# Atmega16-platform.net
KiCad netlist of a schematic drawn in Altium Designer
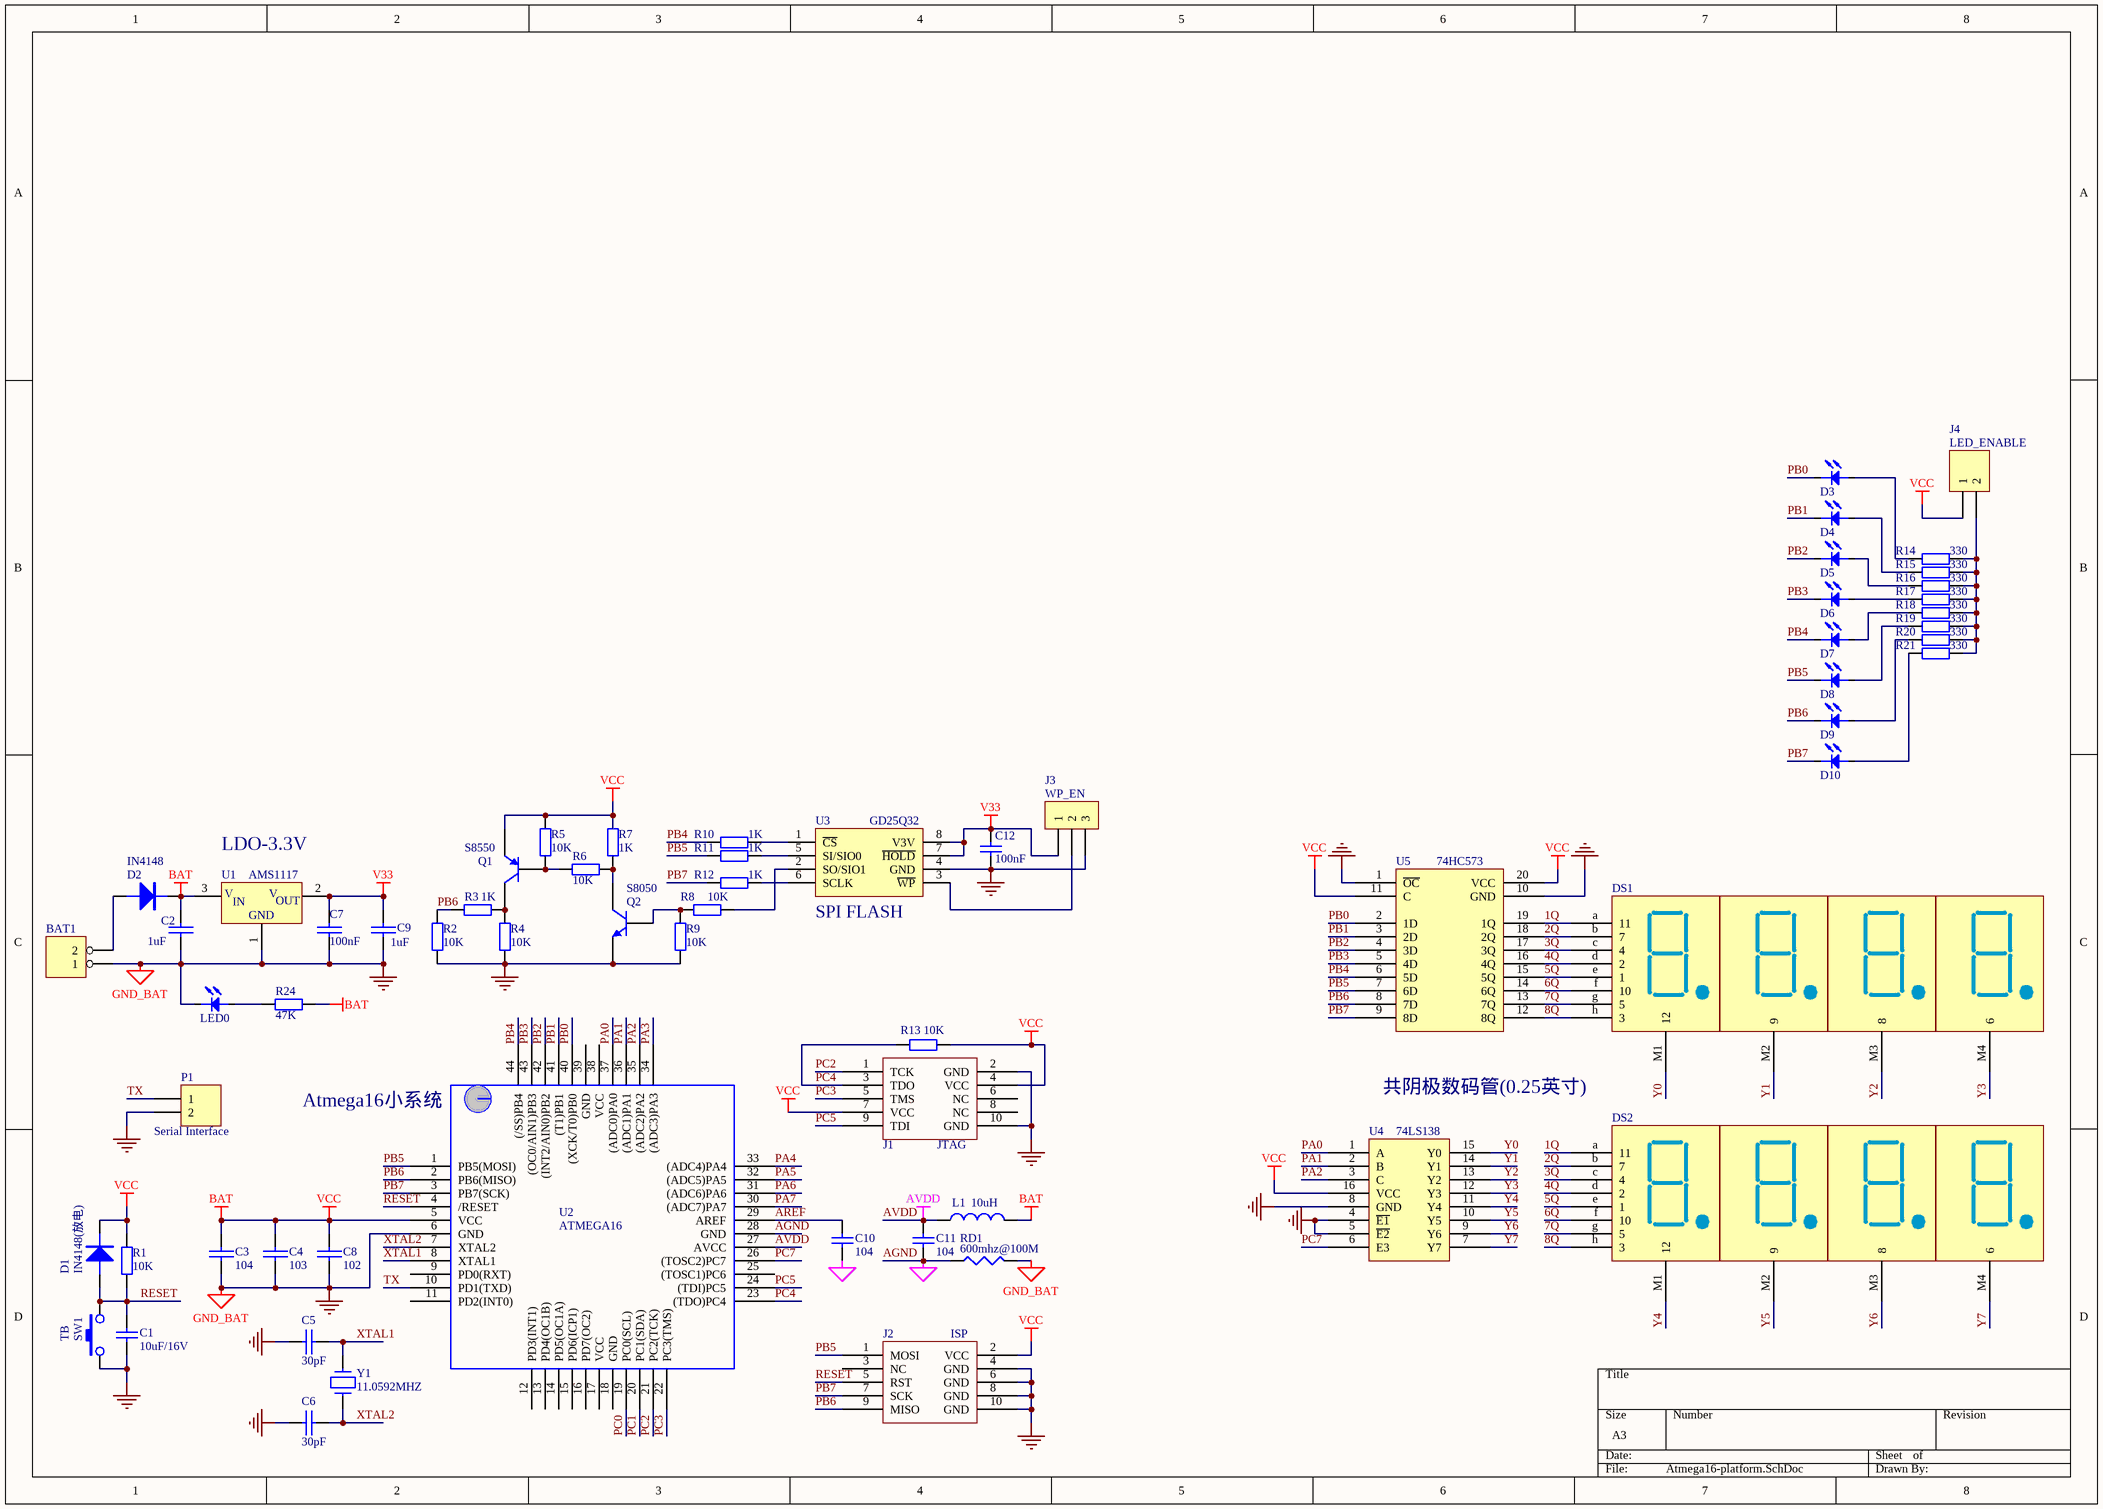
[diagram p0: Atmega16-platform.SchDoc]

(export (version "E")
  (design (tool "Eeschema 10.0.6"))
  (components
    (comp (ref "BAT1") (value "~") (footprint "SIP2") (libsource (lib "*") (part "HEADER 2")))
    (comp (ref "C1")
      (value "10uF/16V")
      (footprint "10uF/50V")
      (description "Capacitor")
      (fields (field (name "PUBLISHER") "Altium Limited"))
      (libsource (lib "*") (part "Cap"))
    )
    (comp (ref "C2")
      (value "1uF")
      (footprint "0805")
      (description "Capacitor")
      (libsource (lib "*") (part "CAP"))
    )
    (comp (ref "C3")
      (value "104")
      (footprint "0603")
      (description "Capacitor")
      (libsource (lib "*") (part "CAP"))
    )
    (comp (ref "C4")
      (value "103")
      (footprint "0603")
      (description "Capacitor")
      (libsource (lib "*") (part "CAP"))
    )
    (comp (ref "C5")
      (value "30pF")
      (footprint "0603")
      (description "Capacitor")
      (libsource (lib "*") (part "CAP"))
    )
    (comp (ref "C6")
      (value "30pF")
      (footprint "0603")
      (description "Capacitor")
      (libsource (lib "*") (part "CAP"))
    )
    (comp (ref "C7")
      (value "100nF")
      (footprint "0603")
      (description "Capacitor")
      (libsource (lib "*") (part "CAP"))
    )
    (comp (ref "C8")
      (value "102")
      (footprint "0603")
      (description "Capacitor")
      (libsource (lib "*") (part "CAP"))
    )
    (comp (ref "C9")
      (value "1uF")
      (footprint "0805")
      (description "Capacitor")
      (libsource (lib "*") (part "CAP"))
    )
    (comp (ref "C10")
      (value "104")
      (footprint "0603")
      (description "Capacitor (Semiconductor SIM Model)")
      (fields (field (name "PUBLISHER") "Altium Limited"))
      (libsource (lib "*") (part "Cap Semi"))
    )
    (comp (ref "C11")
      (value "104")
      (footprint "0603")
      (description "Capacitor (Semiconductor SIM Model)")
      (fields (field (name "PUBLISHER") "Altium Limited"))
      (libsource (lib "*") (part "Cap Semi"))
    )
    (comp (ref "C12")
      (value "100nF")
      (footprint "0603")
      (description "Capacitor")
      (fields (field (name "PUBLISHER") "Altium Limited"))
      (libsource (lib "*") (part "Cap"))
    )
    (comp (ref "D1")
      (value "IN4148(放电)")
      (footprint "SOD-123")
      (description "Diode")
      (libsource (lib "*") (part "DIODE"))
    )
    (comp (ref "D2")
      (value "IN4148")
      (footprint "SOD-123")
      (description "Diode")
      (libsource (lib "*") (part "DIODE"))
    )
    (comp (ref "D3") (value "LED") (footprint "0603") (libsource (lib "常用元件库") (part "LED")))
    (comp (ref "D4") (value "LED") (footprint "0603") (libsource (lib "常用元件库") (part "LED")))
    (comp (ref "D5") (value "LED") (footprint "0603") (libsource (lib "常用元件库") (part "LED")))
    (comp (ref "D6") (value "LED") (footprint "0603") (libsource (lib "常用元件库") (part "LED")))
    (comp (ref "D7") (value "LED") (footprint "0603") (libsource (lib "常用元件库") (part "LED")))
    (comp (ref "D8") (value "LED") (footprint "0603") (libsource (lib "常用元件库") (part "LED")))
    (comp (ref "D9") (value "LED") (footprint "0603") (libsource (lib "常用元件库") (part "LED")))
    (comp (ref "D10") (value "LED") (footprint "0603") (libsource (lib "常用元件库") (part "LED")))
    (comp (ref "DS1")
      (value "LED_8*4_SEG")
      (footprint "4BIT_8SEG_LED")
      (libsource (lib "单片机及相关") (part "LED_8*4_SEG"))
    )
    (comp (ref "DS2")
      (value "LED_8*4_SEG")
      (footprint "4BIT_8SEG_LED")
      (libsource (lib "单片机及相关") (part "LED_8*4_SEG"))
    )
    (comp (ref "J1") (value "JTAG") (footprint "Jtag-10") (libsource (lib "单片机及相关") (part "JTAG")))
    (comp (ref "J2") (value "ISP") (footprint "Jtag-10") (libsource (lib "单片机及相关") (part "ISP")))
    (comp (ref "J3") (value "WP_EN") (footprint "SIP3") (libsource (lib "常用元件库") (part "CON3")))
    (comp (ref "J4")
      (value "LED_ENABLE")
      (footprint "SIP2")
      (description "Header, 2-Pin")
      (fields (field (name "PUBLISHER") "Altium Limited"))
      (libsource (lib "") (part "Header 2_1"))
    )
    (comp (ref "L1") (value "10uH") (footprint "0603") (libsource (lib "*") (part "BEAD")))
    (comp (ref "LED0") (value "LED") (footprint "0603") (libsource (lib "常用元件库") (part "LED")))
    (comp (ref "P1")
      (value "Serial Interface")
      (footprint "SIP2")
      (description "Header, 2-Pin")
      (fields (field (name "PUBLISHER") "Altium Limited"))
      (libsource (lib "Miscellaneous Connectors") (part "Header 2"))
    )
    (comp (ref "Q1")
      (value "S8550")
      (footprint "TO-92A")
      (description "PNP General Purpose Amplifier")
      (fields (field (name "PUBLISHER") "Altium Limited"))
      (libsource (lib "Miscellaneous Devices") (part "2N3906"))
    )
    (comp (ref "Q2")
      (value "S8050")
      (footprint "TO-92A")
      (description "NPN General Purpose Amplifier")
      (fields (field (name "PUBLISHER") "Altium Limited"))
      (libsource (lib "Miscellaneous Devices") (part "2N3904"))
    )
    (comp (ref "R1")
      (value "10K")
      (footprint "0603")
      (description "Resistor")
      (fields (field (name "Comment") "Res2") (field (name "PUBLISHER") "Altium Limited"))
      (libsource (lib "") (part "Res2_1"))
    )
    (comp (ref "R2")
      (value "10K")
      (footprint "0603")
      (description "Resistor")
      (fields (field (name "Comment") "Res2") (field (name "PUBLISHER") "Altium Limited"))
      (libsource (lib "") (part "Res2_3"))
    )
    (comp (ref "R3")
      (value "1K")
      (footprint "0603")
      (description "Resistor")
      (fields (field (name "Comment") "Res2") (field (name "PUBLISHER") "Altium Limited"))
      (libsource (lib "Miscellaneous Devices") (part "Res2"))
    )
    (comp (ref "R4")
      (value "10K")
      (footprint "0603")
      (description "Resistor")
      (fields (field (name "Comment") "Res2") (field (name "PUBLISHER") "Altium Limited"))
      (libsource (lib "") (part "Res2_3"))
    )
    (comp (ref "R5")
      (value "10K")
      (footprint "0603")
      (description "Resistor")
      (fields (field (name "Comment") "Res2") (field (name "PUBLISHER") "Altium Limited"))
      (libsource (lib "") (part "Res2_1"))
    )
    (comp (ref "R6")
      (value "10K")
      (footprint "0603")
      (description "Resistor")
      (fields (field (name "Comment") "Res2") (field (name "PUBLISHER") "Altium Limited"))
      (libsource (lib "") (part "Res2_2"))
    )
    (comp (ref "R7")
      (value "1K")
      (footprint "0603")
      (description "Resistor")
      (fields (field (name "Comment") "Res2") (field (name "PUBLISHER") "Altium Limited"))
      (libsource (lib "") (part "Res2_1"))
    )
    (comp (ref "R8")
      (value "10K")
      (footprint "0603")
      (description "Resistor")
      (fields (field (name "Comment") "Res2") (field (name "PUBLISHER") "Altium Limited"))
      (libsource (lib "") (part "Res2_2"))
    )
    (comp (ref "R9")
      (value "10K")
      (footprint "0603")
      (description "Resistor")
      (fields (field (name "Comment") "Res2") (field (name "PUBLISHER") "Altium Limited"))
      (libsource (lib "") (part "Res2_3"))
    )
    (comp (ref "R10")
      (value "1K")
      (footprint "0603")
      (description "Resistor")
      (fields (field (name "Comment") "Res2") (field (name "PUBLISHER") "Altium Limited"))
      (libsource (lib "Miscellaneous Devices") (part "Res2"))
    )
    (comp (ref "R11")
      (value "1K")
      (footprint "0603")
      (description "Resistor")
      (fields (field (name "Comment") "Res2") (field (name "PUBLISHER") "Altium Limited"))
      (libsource (lib "Miscellaneous Devices") (part "Res2"))
    )
    (comp (ref "R12")
      (value "1K")
      (footprint "0603")
      (description "Resistor")
      (fields (field (name "Comment") "Res2") (field (name "PUBLISHER") "Altium Limited"))
      (libsource (lib "Miscellaneous Devices") (part "Res2"))
    )
    (comp (ref "R13")
      (value "10K")
      (footprint "0603")
      (description "Resistor")
      (fields (field (name "Comment") "Res2") (field (name "PUBLISHER") "Altium Limited"))
      (libsource (lib "Miscellaneous Devices") (part "Res2"))
    )
    (comp (ref "R14")
      (value "330")
      (footprint "0603")
      (description "Resistor")
      (fields (field (name "Comment") "Res2") (field (name "PUBLISHER") "Altium Limited"))
      (libsource (lib "Miscellaneous Devices") (part "Res2"))
    )
    (comp (ref "R15")
      (value "330")
      (footprint "0603")
      (description "Resistor")
      (fields (field (name "Comment") "Res2") (field (name "PUBLISHER") "Altium Limited"))
      (libsource (lib "Miscellaneous Devices") (part "Res2"))
    )
    (comp (ref "R16")
      (value "330")
      (footprint "0603")
      (description "Resistor")
      (fields (field (name "Comment") "Res2") (field (name "PUBLISHER") "Altium Limited"))
      (libsource (lib "Miscellaneous Devices") (part "Res2"))
    )
    (comp (ref "R17")
      (value "330")
      (footprint "0603")
      (description "Resistor")
      (fields (field (name "Comment") "Res2") (field (name "PUBLISHER") "Altium Limited"))
      (libsource (lib "Miscellaneous Devices") (part "Res2"))
    )
    (comp (ref "R18")
      (value "330")
      (footprint "0603")
      (description "Resistor")
      (fields (field (name "Comment") "Res2") (field (name "PUBLISHER") "Altium Limited"))
      (libsource (lib "Miscellaneous Devices") (part "Res2"))
    )
    (comp (ref "R19")
      (value "330")
      (footprint "0603")
      (description "Resistor")
      (fields (field (name "Comment") "Res2") (field (name "PUBLISHER") "Altium Limited"))
      (libsource (lib "Miscellaneous Devices") (part "Res2"))
    )
    (comp (ref "R20")
      (value "330")
      (footprint "0603")
      (description "Resistor")
      (fields (field (name "Comment") "Res2") (field (name "PUBLISHER") "Altium Limited"))
      (libsource (lib "Miscellaneous Devices") (part "Res2"))
    )
    (comp (ref "R21")
      (value "330")
      (footprint "0603")
      (description "Resistor")
      (fields (field (name "Comment") "Res2") (field (name "PUBLISHER") "Altium Limited"))
      (libsource (lib "Miscellaneous Devices") (part "Res2"))
    )
    (comp (ref "R24")
      (value "47K")
      (footprint "0603")
      (description "Resistor")
      (fields (field (name "Comment") "Res2") (field (name "PUBLISHER") "Altium Limited"))
      (libsource (lib "") (part "Res2_2"))
    )
    (comp (ref "RD1") (value "600mhz@100M") (footprint "0603") (libsource (lib "*") (part "RES")))
    (comp (ref "SW1") (value "TB") (footprint "AN66") (libsource (lib "*") (part "SW-PB")))
    (comp (ref "U1") (value "AMS1117") (footprint "SOT223") (libsource (lib "78稳压块") (part "AMS1117")))
    (comp (ref "U2") (value "ATMEGA16") (footprint "TQFP-44A") (libsource (lib "manonC") (part "ATMEGA16")))
    (comp (ref "U3") (value "GD25Q32") (footprint "SO-8") (libsource (lib "manonC") (part "GD25Q32")))
    (comp (ref "U4") (value "74LS138") (footprint "SOT403-1_N") (libsource (lib "manonC") (part "74LS138")))
    (comp (ref "U5") (value "74HC573") (footprint "SOT339-1") (libsource (lib "manonC") (part "74HC573")))
    (comp (ref "Y1")
      (value "11.0592MHZ")
      (footprint "XTAL")
      (description "Crystal")
      (libsource (lib "*") (part "CRYSTAL"))
    )
  )
  (nets
    (net (code "1") (name "/1Q") (class "Default")
      (node (ref "DS1") (pin "a") (pinfunction "11_a") (pintype "passive"))
      (node (ref "DS2") (pin "a") (pinfunction "11_a") (pintype "passive"))
      (node (ref "U5") (pin "19") (pinfunction "1Q_19") (pintype "passive"))
    )
    (net (code "2") (name "/2Q") (class "Default")
      (node (ref "DS1") (pin "b") (pinfunction "7_b") (pintype "passive"))
      (node (ref "DS2") (pin "b") (pinfunction "7_b") (pintype "passive"))
      (node (ref "U5") (pin "18") (pinfunction "2Q_18") (pintype "passive"))
    )
    (net (code "3") (name "/3Q") (class "Default")
      (node (ref "DS1") (pin "c") (pinfunction "4_c") (pintype "passive"))
      (node (ref "DS2") (pin "c") (pinfunction "4_c") (pintype "passive"))
      (node (ref "U5") (pin "17") (pinfunction "3Q_17") (pintype "passive"))
    )
    (net (code "4") (name "/4Q") (class "Default")
      (node (ref "DS1") (pin "d") (pinfunction "2_d") (pintype "passive"))
      (node (ref "DS2") (pin "d") (pinfunction "2_d") (pintype "passive"))
      (node (ref "U5") (pin "16") (pinfunction "4Q_16") (pintype "passive"))
    )
    (net (code "5") (name "/5Q") (class "Default")
      (node (ref "DS1") (pin "e") (pinfunction "1_e") (pintype "passive"))
      (node (ref "DS2") (pin "e") (pinfunction "1_e") (pintype "passive"))
      (node (ref "U5") (pin "15") (pinfunction "5Q_15") (pintype "passive"))
    )
    (net (code "6") (name "/6Q") (class "Default")
      (node (ref "DS1") (pin "f") (pinfunction "10_f") (pintype "passive"))
      (node (ref "DS2") (pin "f") (pinfunction "10_f") (pintype "passive"))
      (node (ref "U5") (pin "14") (pinfunction "6Q_14") (pintype "passive"))
    )
    (net (code "7") (name "/7Q") (class "Default")
      (node (ref "DS1") (pin "g") (pinfunction "5_g") (pintype "passive"))
      (node (ref "DS2") (pin "g") (pinfunction "5_g") (pintype "passive"))
      (node (ref "U5") (pin "13") (pinfunction "7Q_13") (pintype "passive"))
    )
    (net (code "8") (name "/8Q") (class "Default")
      (node (ref "DS1") (pin "h") (pinfunction "3_h") (pintype "passive"))
      (node (ref "DS2") (pin "h") (pinfunction "3_h") (pintype "passive"))
      (node (ref "U5") (pin "12") (pinfunction "8Q_12") (pintype "passive"))
    )
    (net (code "9") (name "/AREF") (class "Default")
      (node (ref "C10") (pin "2") (pinfunction "2_2") (pintype "passive"))
      (node (ref "U2") (pin "29") (pinfunction "AREF_29") (pintype "passive"))
    )
    (net (code "10") (name "/PA0") (class "Default")
      (node (ref "U2") (pin "37") (pinfunction "(ADC0)PA0_37") (pintype "passive"))
      (node (ref "U4") (pin "1") (pinfunction "A_1") (pintype "passive"))
    )
    (net (code "11") (name "/PA1") (class "Default")
      (node (ref "U2") (pin "36") (pinfunction "(ADC1)PA1_36") (pintype "passive"))
      (node (ref "U4") (pin "2") (pinfunction "B_2") (pintype "passive"))
    )
    (net (code "12") (name "/PA2") (class "Default")
      (node (ref "U2") (pin "35") (pinfunction "(ADC2)PA2_35") (pintype "passive"))
      (node (ref "U4") (pin "3") (pinfunction "C_3") (pintype "passive"))
    )
    (net (code "13") (name "/PA3") (class "Default")
      (node (ref "U2") (pin "34") (pinfunction "(ADC3)PA3_34") (pintype "passive"))
    )
    (net (code "14") (name "/PA4") (class "Default")
      (node (ref "U2") (pin "33") (pinfunction "(ADC4)PA4_33") (pintype "passive"))
    )
    (net (code "15") (name "/PA5") (class "Default")
      (node (ref "U2") (pin "32") (pinfunction "(ADC5)PA5_32") (pintype "passive"))
    )
    (net (code "16") (name "/PA6") (class "Default")
      (node (ref "U2") (pin "31") (pinfunction "(ADC6)PA6_31") (pintype "passive"))
    )
    (net (code "17") (name "/PA7") (class "Default")
      (node (ref "U2") (pin "30") (pinfunction "(ADC7)PA7_30") (pintype "passive"))
    )
    (net (code "18") (name "/PB0") (class "Default")
      (node (ref "D3") (pin "2") (pintype "passive"))
      (node (ref "U2") (pin "40") (pinfunction "(XCK/T0)PB0_40") (pintype "passive"))
      (node (ref "U5") (pin "2") (pinfunction "1D_2") (pintype "passive"))
    )
    (net (code "19") (name "/PB1") (class "Default")
      (node (ref "D4") (pin "2") (pintype "passive"))
      (node (ref "U2") (pin "41") (pinfunction "(T1)PB1_41") (pintype "passive"))
      (node (ref "U5") (pin "3") (pinfunction "2D_3") (pintype "passive"))
    )
    (net (code "20") (name "/PB2") (class "Default")
      (node (ref "D5") (pin "2") (pintype "passive"))
      (node (ref "U2") (pin "42") (pinfunction "(INT2/AIN0)PB2_42") (pintype "passive"))
      (node (ref "U5") (pin "4") (pinfunction "3D_4") (pintype "passive"))
    )
    (net (code "21") (name "/PB3") (class "Default")
      (node (ref "D6") (pin "2") (pintype "passive"))
      (node (ref "U2") (pin "43") (pinfunction "(OC0/AIN1)PB3_43") (pintype "passive"))
      (node (ref "U5") (pin "5") (pinfunction "4D_5") (pintype "passive"))
    )
    (net (code "22") (name "/PB4") (class "Default")
      (node (ref "D7") (pin "2") (pintype "passive"))
      (node (ref "R10") (pin "1") (pinfunction "1_1") (pintype "passive"))
      (node (ref "U2") (pin "44") (pinfunction "(/SS)PB4_44") (pintype "passive"))
      (node (ref "U5") (pin "6") (pinfunction "5D_6") (pintype "passive"))
    )
    (net (code "23") (name "/PB5") (class "Default")
      (node (ref "D8") (pin "2") (pintype "passive"))
      (node (ref "J2") (pin "1") (pinfunction "MOSI_1") (pintype "passive"))
      (node (ref "R11") (pin "1") (pinfunction "1_1") (pintype "passive"))
      (node (ref "U2") (pin "1") (pinfunction "PB5(MOSI)_1") (pintype "passive"))
      (node (ref "U5") (pin "7") (pinfunction "6D_7") (pintype "passive"))
    )
    (net (code "24") (name "/PB6") (class "Default")
      (node (ref "D9") (pin "2") (pintype "passive"))
      (node (ref "J2") (pin "9") (pinfunction "MISO_9") (pintype "passive"))
      (node (ref "R2") (pin "1") (pinfunction "1_1") (pintype "passive"))
      (node (ref "R3") (pin "1") (pinfunction "1_1") (pintype "passive"))
      (node (ref "U2") (pin "2") (pinfunction "PB6(MISO)_2") (pintype "passive"))
      (node (ref "U5") (pin "8") (pinfunction "7D_8") (pintype "passive"))
    )
    (net (code "25") (name "/PB7") (class "Default")
      (node (ref "D10") (pin "2") (pintype "passive"))
      (node (ref "J2") (pin "7") (pinfunction "SCK_7") (pintype "passive"))
      (node (ref "R12") (pin "1") (pinfunction "1_1") (pintype "passive"))
      (node (ref "U2") (pin "3") (pinfunction "PB7(SCK)_3") (pintype "passive"))
      (node (ref "U5") (pin "9") (pinfunction "8D_9") (pintype "passive"))
    )
    (net (code "26") (name "/PC0") (class "Default")
      (node (ref "U2") (pin "19") (pinfunction "PC0(SCL)_19") (pintype "passive"))
    )
    (net (code "27") (name "/PC1") (class "Default")
      (node (ref "U2") (pin "20") (pinfunction "PC1(SDA)_20") (pintype "passive"))
    )
    (net (code "28") (name "/PC2") (class "Default")
      (node (ref "J1") (pin "1") (pinfunction "TCK_1") (pintype "passive"))
      (node (ref "U2") (pin "21") (pinfunction "PC2(TCK)_21") (pintype "passive"))
    )
    (net (code "29") (name "/PC3") (class "Default")
      (node (ref "J1") (pin "5") (pinfunction "TMS_5") (pintype "passive"))
      (node (ref "U2") (pin "22") (pinfunction "PC3(TMS)_22") (pintype "passive"))
    )
    (net (code "30") (name "/PC4") (class "Default")
      (node (ref "J1") (pin "3") (pinfunction "TDO_3") (pintype "passive"))
      (node (ref "R13") (pin "1") (pinfunction "1_1") (pintype "passive"))
      (node (ref "U2") (pin "23") (pinfunction "(TDO)PC4_23") (pintype "passive"))
    )
    (net (code "31") (name "/PC5") (class "Default")
      (node (ref "J1") (pin "9") (pinfunction "TDI_9") (pintype "passive"))
      (node (ref "U2") (pin "24") (pinfunction "(TDI)PC5_24") (pintype "passive"))
    )
    (net (code "32") (name "/PC7") (class "Default")
      (node (ref "U2") (pin "26") (pinfunction "(TOSC2)PC7_26") (pintype "passive"))
      (node (ref "U4") (pin "6") (pinfunction "E3_6") (pintype "passive"))
    )
    (net (code "33") (name "/RESET") (class "Default")
      (node (ref "C1") (pin "1") (pinfunction "1_1") (pintype "passive"))
      (node (ref "D1") (pin "1") (pinfunction "A_1") (pintype "passive"))
      (node (ref "J2") (pin "5") (pinfunction "RST_5") (pintype "passive"))
      (node (ref "R1") (pin "1") (pinfunction "1_1") (pintype "passive"))
      (node (ref "SW1") (pin "2") (pinfunction "2_2") (pintype "passive"))
      (node (ref "U2") (pin "4") (pinfunction "/RESET_4") (pintype "passive"))
    )
    (net (code "34") (name "/TX") (class "Default")
      (node (ref "P1") (pin "1") (pinfunction "1_1") (pintype "passive"))
      (node (ref "U2") (pin "10") (pinfunction "PD1(TXD)_10") (pintype "passive"))
    )
    (net (code "35") (name "/XTAL1") (class "Default")
      (node (ref "C5") (pin "1") (pinfunction "1_1") (pintype "passive"))
      (node (ref "U2") (pin "8") (pinfunction "XTAL1_8") (pintype "passive"))
      (node (ref "Y1") (pin "1") (pinfunction "1_1") (pintype "passive"))
    )
    (net (code "36") (name "/XTAL2") (class "Default")
      (node (ref "C6") (pin "1") (pinfunction "1_1") (pintype "passive"))
      (node (ref "U2") (pin "7") (pinfunction "XTAL2_7") (pintype "passive"))
      (node (ref "Y1") (pin "2") (pinfunction "2_2") (pintype "passive"))
    )
    (net (code "37") (name "/Y0") (class "Default")
      (node (ref "DS1") (pin "M1") (pinfunction "12_M1") (pintype "passive"))
      (node (ref "U4") (pin "15") (pinfunction "Y0_15") (pintype "passive"))
    )
    (net (code "38") (name "/Y1") (class "Default")
      (node (ref "DS1") (pin "M2") (pinfunction "9_M2") (pintype "passive"))
      (node (ref "U4") (pin "14") (pinfunction "Y1_14") (pintype "passive"))
    )
    (net (code "39") (name "/Y2") (class "Default")
      (node (ref "DS1") (pin "M3") (pinfunction "8_M3") (pintype "passive"))
      (node (ref "U4") (pin "13") (pinfunction "Y2_13") (pintype "passive"))
    )
    (net (code "40") (name "/Y3") (class "Default")
      (node (ref "DS1") (pin "M4") (pinfunction "6_M4") (pintype "passive"))
      (node (ref "U4") (pin "12") (pinfunction "Y3_12") (pintype "passive"))
    )
    (net (code "41") (name "/Y4") (class "Default")
      (node (ref "DS2") (pin "M1") (pinfunction "12_M1") (pintype "passive"))
      (node (ref "U4") (pin "11") (pinfunction "Y4_11") (pintype "passive"))
    )
    (net (code "42") (name "/Y5") (class "Default")
      (node (ref "DS2") (pin "M2") (pinfunction "9_M2") (pintype "passive"))
      (node (ref "U4") (pin "10") (pinfunction "Y5_10") (pintype "passive"))
    )
    (net (code "43") (name "/Y6") (class "Default")
      (node (ref "DS2") (pin "M3") (pinfunction "8_M3") (pintype "passive"))
      (node (ref "U4") (pin "9") (pinfunction "Y6_9") (pintype "passive"))
    )
    (net (code "44") (name "/Y7") (class "Default")
      (node (ref "DS2") (pin "M4") (pinfunction "6_M4") (pintype "passive"))
      (node (ref "U4") (pin "7") (pinfunction "Y7_7") (pintype "passive"))
    )
    (net (code "45") (name "AGND") (class "Default")
      (node (ref "C10") (pin "1") (pinfunction "1_1") (pintype "passive"))
      (node (ref "C11") (pin "1") (pinfunction "1_1") (pintype "passive"))
      (node (ref "RD1") (pin "1") (pinfunction "1_1") (pintype "passive"))
      (node (ref "U2") (pin "28") (pinfunction "GND_28") (pintype "passive"))
    )
    (net (code "46") (name "AVDD") (class "Default")
      (node (ref "C11") (pin "2") (pinfunction "2_2") (pintype "passive"))
      (node (ref "L1") (pin "2") (pinfunction "2_2") (pintype "passive"))
      (node (ref "U2") (pin "27") (pinfunction "AVCC_27") (pintype "passive"))
    )
    (net (code "47") (name "BAT") (class "Default")
      (node (ref "C2") (pin "1") (pinfunction "1_1") (pintype "passive"))
      (node (ref "C3") (pin "1") (pinfunction "1_1") (pintype "passive"))
      (node (ref "C4") (pin "1") (pinfunction "1_1") (pintype "passive"))
      (node (ref "C8") (pin "1") (pinfunction "1_1") (pintype "passive"))
      (node (ref "D1") (pin "2") (pinfunction "K_2") (pintype "passive"))
      (node (ref "D2") (pin "2") (pinfunction "K_2") (pintype "passive"))
      (node (ref "J1") (pin "4") (pinfunction "VCC_4") (pintype "passive"))
      (node (ref "J1") (pin "7") (pinfunction "VCC_7") (pintype "passive"))
      (node (ref "J2") (pin "2") (pinfunction "VCC_2") (pintype "passive"))
      (node (ref "J4") (pin "1") (pinfunction "1_1") (pintype "passive"))
      (node (ref "L1") (pin "1") (pinfunction "1_1") (pintype "passive"))
      (node (ref "Q1") (pin "1") (pinfunction "E_1") (pintype "passive"))
      (node (ref "R1") (pin "2") (pinfunction "2_2") (pintype "passive"))
      (node (ref "R13") (pin "2") (pinfunction "2_2") (pintype "passive"))
      (node (ref "R24") (pin "1") (pinfunction "1_1") (pintype "passive"))
      (node (ref "R5") (pin "2") (pinfunction "2_2") (pintype "passive"))
      (node (ref "R7") (pin "2") (pinfunction "2_2") (pintype "passive"))
      (node (ref "U1") (pin "3") (pinfunction "VIN_3") (pintype "passive"))
      (node (ref "U2") (pin "5") (pinfunction "VCC_5") (pintype "passive"))
      (node (ref "U4") (pin "16") (pinfunction "VCC_16") (pintype "power_in"))
      (node (ref "U5") (pin "11") (pinfunction "C_11") (pintype "passive"))
      (node (ref "U5") (pin "20") (pinfunction "VCC_20") (pintype "power_in"))
    )
    (net (code "48") (name "GND") (class "Default")
      (node (ref "BAT1") (pin "1") (pinfunction "1_1") (pintype "passive"))
      (node (ref "C1") (pin "2") (pinfunction "2_2") (pintype "passive"))
      (node (ref "C12") (pin "1") (pinfunction "1_1") (pintype "passive"))
      (node (ref "C2") (pin "2") (pinfunction "2_2") (pintype "passive"))
      (node (ref "C3") (pin "2") (pinfunction "2_2") (pintype "passive"))
      (node (ref "C4") (pin "2") (pinfunction "2_2") (pintype "passive"))
      (node (ref "C5") (pin "2") (pinfunction "2_2") (pintype "passive"))
      (node (ref "C6") (pin "2") (pinfunction "2_2") (pintype "passive"))
      (node (ref "C7") (pin "2") (pinfunction "2_2") (pintype "passive"))
      (node (ref "C8") (pin "2") (pinfunction "2_2") (pintype "passive"))
      (node (ref "C9") (pin "2") (pinfunction "2_2") (pintype "passive"))
      (node (ref "J1") (pin "10") (pinfunction "GND_10") (pintype "passive"))
      (node (ref "J1") (pin "2") (pinfunction "GND_2") (pintype "passive"))
      (node (ref "J2") (pin "10") (pinfunction "GND_10") (pintype "passive"))
      (node (ref "J2") (pin "4") (pinfunction "GND_4") (pintype "passive"))
      (node (ref "J2") (pin "6") (pinfunction "GND_6") (pintype "passive"))
      (node (ref "J2") (pin "8") (pinfunction "GND_8") (pintype "passive"))
      (node (ref "J3") (pin "3") (pinfunction "3_3") (pintype "passive"))
      (node (ref "LED0") (pin "2") (pintype "passive"))
      (node (ref "P1") (pin "2") (pinfunction "2_2") (pintype "passive"))
      (node (ref "Q2") (pin "1") (pinfunction "E_1") (pintype "passive"))
      (node (ref "R2") (pin "2") (pinfunction "2_2") (pintype "passive"))
      (node (ref "R4") (pin "2") (pinfunction "2_2") (pintype "passive"))
      (node (ref "R9") (pin "2") (pinfunction "2_2") (pintype "passive"))
      (node (ref "RD1") (pin "2") (pinfunction "2_2") (pintype "passive"))
      (node (ref "SW1") (pin "1") (pinfunction "1_1") (pintype "passive"))
      (node (ref "U1") (pin "1") (pinfunction "GND_1") (pintype "passive"))
      (node (ref "U2") (pin "6") (pinfunction "GND_6") (pintype "passive"))
      (node (ref "U3") (pin "4") (pinfunction "GND_4") (pintype "passive"))
      (node (ref "U4") (pin "4") (pinfunction "~{E1}_4") (pintype "passive"))
      (node (ref "U4") (pin "5") (pinfunction "~{E2}_5") (pintype "passive"))
      (node (ref "U4") (pin "8") (pinfunction "GND_8") (pintype "power_in"))
      (node (ref "U5") (pin "1") (pinfunction "~{OC}_1") (pintype "passive"))
      (node (ref "U5") (pin "10") (pinfunction "GND_10") (pintype "power_in"))
    )
    (net (code "49") (name "Net-(D2-A)") (class "Default")
      (node (ref "BAT1") (pin "2") (pinfunction "2_2") (pintype "passive"))
      (node (ref "D2") (pin "1") (pinfunction "A_1") (pintype "passive"))
    )
    (net (code "50") (name "Net-(D3-Pad1)") (class "Default")
      (node (ref "D3") (pin "1") (pintype "passive"))
      (node (ref "R14") (pin "1") (pinfunction "1_1") (pintype "passive"))
    )
    (net (code "51") (name "Net-(D4-Pad1)") (class "Default")
      (node (ref "D4") (pin "1") (pintype "passive"))
      (node (ref "R15") (pin "1") (pinfunction "1_1") (pintype "passive"))
    )
    (net (code "52") (name "Net-(D5-Pad1)") (class "Default")
      (node (ref "D5") (pin "1") (pintype "passive"))
      (node (ref "R16") (pin "1") (pinfunction "1_1") (pintype "passive"))
    )
    (net (code "53") (name "Net-(D6-Pad1)") (class "Default")
      (node (ref "D6") (pin "1") (pintype "passive"))
      (node (ref "R17") (pin "1") (pinfunction "1_1") (pintype "passive"))
    )
    (net (code "54") (name "Net-(D7-Pad1)") (class "Default")
      (node (ref "D7") (pin "1") (pintype "passive"))
      (node (ref "R18") (pin "1") (pinfunction "1_1") (pintype "passive"))
    )
    (net (code "55") (name "Net-(D8-Pad1)") (class "Default")
      (node (ref "D8") (pin "1") (pintype "passive"))
      (node (ref "R19") (pin "1") (pinfunction "1_1") (pintype "passive"))
    )
    (net (code "56") (name "Net-(D9-Pad1)") (class "Default")
      (node (ref "D9") (pin "1") (pintype "passive"))
      (node (ref "R20") (pin "1") (pinfunction "1_1") (pintype "passive"))
    )
    (net (code "57") (name "Net-(D10-Pad1)") (class "Default")
      (node (ref "D10") (pin "1") (pintype "passive"))
      (node (ref "R21") (pin "1") (pinfunction "1_1") (pintype "passive"))
    )
    (net (code "58") (name "Net-(J4-Pad2)") (class "Default")
      (node (ref "J4") (pin "2") (pinfunction "2_2") (pintype "passive"))
      (node (ref "R14") (pin "2") (pinfunction "2_2") (pintype "passive"))
      (node (ref "R15") (pin "2") (pinfunction "2_2") (pintype "passive"))
      (node (ref "R16") (pin "2") (pinfunction "2_2") (pintype "passive"))
      (node (ref "R17") (pin "2") (pinfunction "2_2") (pintype "passive"))
      (node (ref "R18") (pin "2") (pinfunction "2_2") (pintype "passive"))
      (node (ref "R19") (pin "2") (pinfunction "2_2") (pintype "passive"))
      (node (ref "R20") (pin "2") (pinfunction "2_2") (pintype "passive"))
      (node (ref "R21") (pin "2") (pinfunction "2_2") (pintype "passive"))
    )
    (net (code "59") (name "Net-(LED0-Pad1)") (class "Default")
      (node (ref "LED0") (pin "1") (pintype "passive"))
      (node (ref "R24") (pin "2") (pinfunction "2_2") (pintype "passive"))
    )
    (net (code "60") (name "Net-(Q1-B)") (class "Default")
      (node (ref "Q1") (pin "2") (pinfunction "B_2") (pintype "passive"))
      (node (ref "R5") (pin "1") (pinfunction "1_1") (pintype "passive"))
      (node (ref "R6") (pin "2") (pinfunction "2_2") (pintype "passive"))
    )
    (net (code "61") (name "Net-(Q1-C)") (class "Default")
      (node (ref "Q1") (pin "3") (pinfunction "C_3") (pintype "passive"))
      (node (ref "R3") (pin "2") (pinfunction "2_2") (pintype "passive"))
      (node (ref "R4") (pin "1") (pinfunction "1_1") (pintype "passive"))
    )
    (net (code "62") (name "Net-(Q2-B)") (class "Default")
      (node (ref "Q2") (pin "2") (pinfunction "B_2") (pintype "passive"))
      (node (ref "R8") (pin "2") (pinfunction "2_2") (pintype "passive"))
      (node (ref "R9") (pin "1") (pinfunction "1_1") (pintype "passive"))
    )
    (net (code "63") (name "Net-(Q2-C)") (class "Default")
      (node (ref "Q2") (pin "3") (pinfunction "C_3") (pintype "passive"))
      (node (ref "R6") (pin "1") (pinfunction "1_1") (pintype "passive"))
      (node (ref "R7") (pin "1") (pinfunction "1_1") (pintype "passive"))
    )
    (net (code "64") (name "Net-(U3-SCLK)") (class "Default")
      (node (ref "R12") (pin "2") (pinfunction "2_2") (pintype "passive"))
      (node (ref "U3") (pin "6") (pinfunction "SCLK_6") (pintype "passive"))
    )
    (net (code "65") (name "Net-(U3-SI{slash}SIO0)") (class "Default")
      (node (ref "R11") (pin "2") (pinfunction "2_2") (pintype "passive"))
      (node (ref "U3") (pin "5") (pinfunction "SI/SIO0_5") (pintype "passive"))
    )
    (net (code "66") (name "Net-(U3-SO{slash}SIO1)") (class "Default")
      (node (ref "R8") (pin "1") (pinfunction "1_1") (pintype "passive"))
      (node (ref "U3") (pin "2") (pinfunction "SO/SIO1_2") (pintype "passive"))
    )
    (net (code "67") (name "Net-(U3-~{CS})") (class "Default")
      (node (ref "R10") (pin "2") (pinfunction "2_2") (pintype "passive"))
      (node (ref "U3") (pin "1") (pinfunction "~{CS}_1") (pintype "passive"))
    )
    (net (code "68") (name "Net-(U3-~{WP})") (class "Default")
      (node (ref "J3") (pin "2") (pinfunction "2_2") (pintype "passive"))
      (node (ref "U3") (pin "3") (pinfunction "~{WP}_3") (pintype "passive"))
    )
    (net (code "69") (name "V33") (class "Default")
      (node (ref "C12") (pin "2") (pinfunction "2_2") (pintype "passive"))
      (node (ref "C7") (pin "1") (pinfunction "1_1") (pintype "passive"))
      (node (ref "C9") (pin "1") (pinfunction "1_1") (pintype "passive"))
      (node (ref "J3") (pin "1") (pinfunction "1_1") (pintype "passive"))
      (node (ref "U1") (pin "2") (pinfunction "VOUT_2") (pintype "passive"))
      (node (ref "U3") (pin "7") (pinfunction "~{HOLD}_7") (pintype "passive"))
      (node (ref "U3") (pin "8") (pinfunction "V3V_8") (pintype "passive"))
    )
    (net (code "70") (name "unconnected-(J1-NC-Pad6)") (class "Default")
      (node (ref "J1") (pin "6") (pinfunction "NC_6") (pintype "passive"))
    )
    (net (code "71") (name "unconnected-(J1-NC-Pad8)") (class "Default")
      (node (ref "J1") (pin "8") (pinfunction "NC_8") (pintype "passive"))
    )
    (net (code "72") (name "unconnected-(J2-NC-Pad3)") (class "Default")
      (node (ref "J2") (pin "3") (pinfunction "NC_3") (pintype "passive"))
    )
    (net (code "73") (name "unconnected-(U2-(TOSC1)PC6-Pad25)") (class "Default")
      (node (ref "U2") (pin "25") (pinfunction "(TOSC1)PC6_25") (pintype "passive"))
    )
    (net (code "74") (name "unconnected-(U2-GND-Pad18)") (class "Default")
      (node (ref "U2") (pin "18") (pinfunction "GND_18") (pintype "passive"))
    )
    (net (code "75") (name "unconnected-(U2-GND-Pad39)") (class "Default")
      (node (ref "U2") (pin "39") (pinfunction "GND_39") (pintype "passive"))
    )
    (net (code "76") (name "unconnected-(U2-PD0(RXT)-Pad9)") (class "Default")
      (node (ref "U2") (pin "9") (pinfunction "PD0(RXT)_9") (pintype "passive"))
    )
    (net (code "77") (name "unconnected-(U2-PD2(INT0)-Pad11)") (class "Default")
      (node (ref "U2") (pin "11") (pinfunction "PD2(INT0)_11") (pintype "passive"))
    )
    (net (code "78") (name "unconnected-(U2-PD3(INT1)-Pad12)") (class "Default")
      (node (ref "U2") (pin "12") (pinfunction "PD3(INT1)_12") (pintype "passive"))
    )
    (net (code "79") (name "unconnected-(U2-PD4(OC1B)-Pad13)") (class "Default")
      (node (ref "U2") (pin "13") (pinfunction "PD4(OC1B)_13") (pintype "passive"))
    )
    (net (code "80") (name "unconnected-(U2-PD5(OC1A)-Pad14)") (class "Default")
      (node (ref "U2") (pin "14") (pinfunction "PD5(OC1A)_14") (pintype "passive"))
    )
    (net (code "81") (name "unconnected-(U2-PD6(ICP1)-Pad15)") (class "Default")
      (node (ref "U2") (pin "15") (pinfunction "PD6(ICP1)_15") (pintype "passive"))
    )
    (net (code "82") (name "unconnected-(U2-PD7(OC2)-Pad16)") (class "Default")
      (node (ref "U2") (pin "16") (pinfunction "PD7(OC2)_16") (pintype "passive"))
    )
    (net (code "83") (name "unconnected-(U2-VCC-Pad17)") (class "Default")
      (node (ref "U2") (pin "17") (pinfunction "VCC_17") (pintype "passive"))
    )
    (net (code "84") (name "unconnected-(U2-VCC-Pad38)") (class "Default")
      (node (ref "U2") (pin "38") (pinfunction "VCC_38") (pintype "passive"))
    )
  )
)
